# QuadPowerDistro_v0.net
KiCad netlist of a schematic drawn in EAGLE
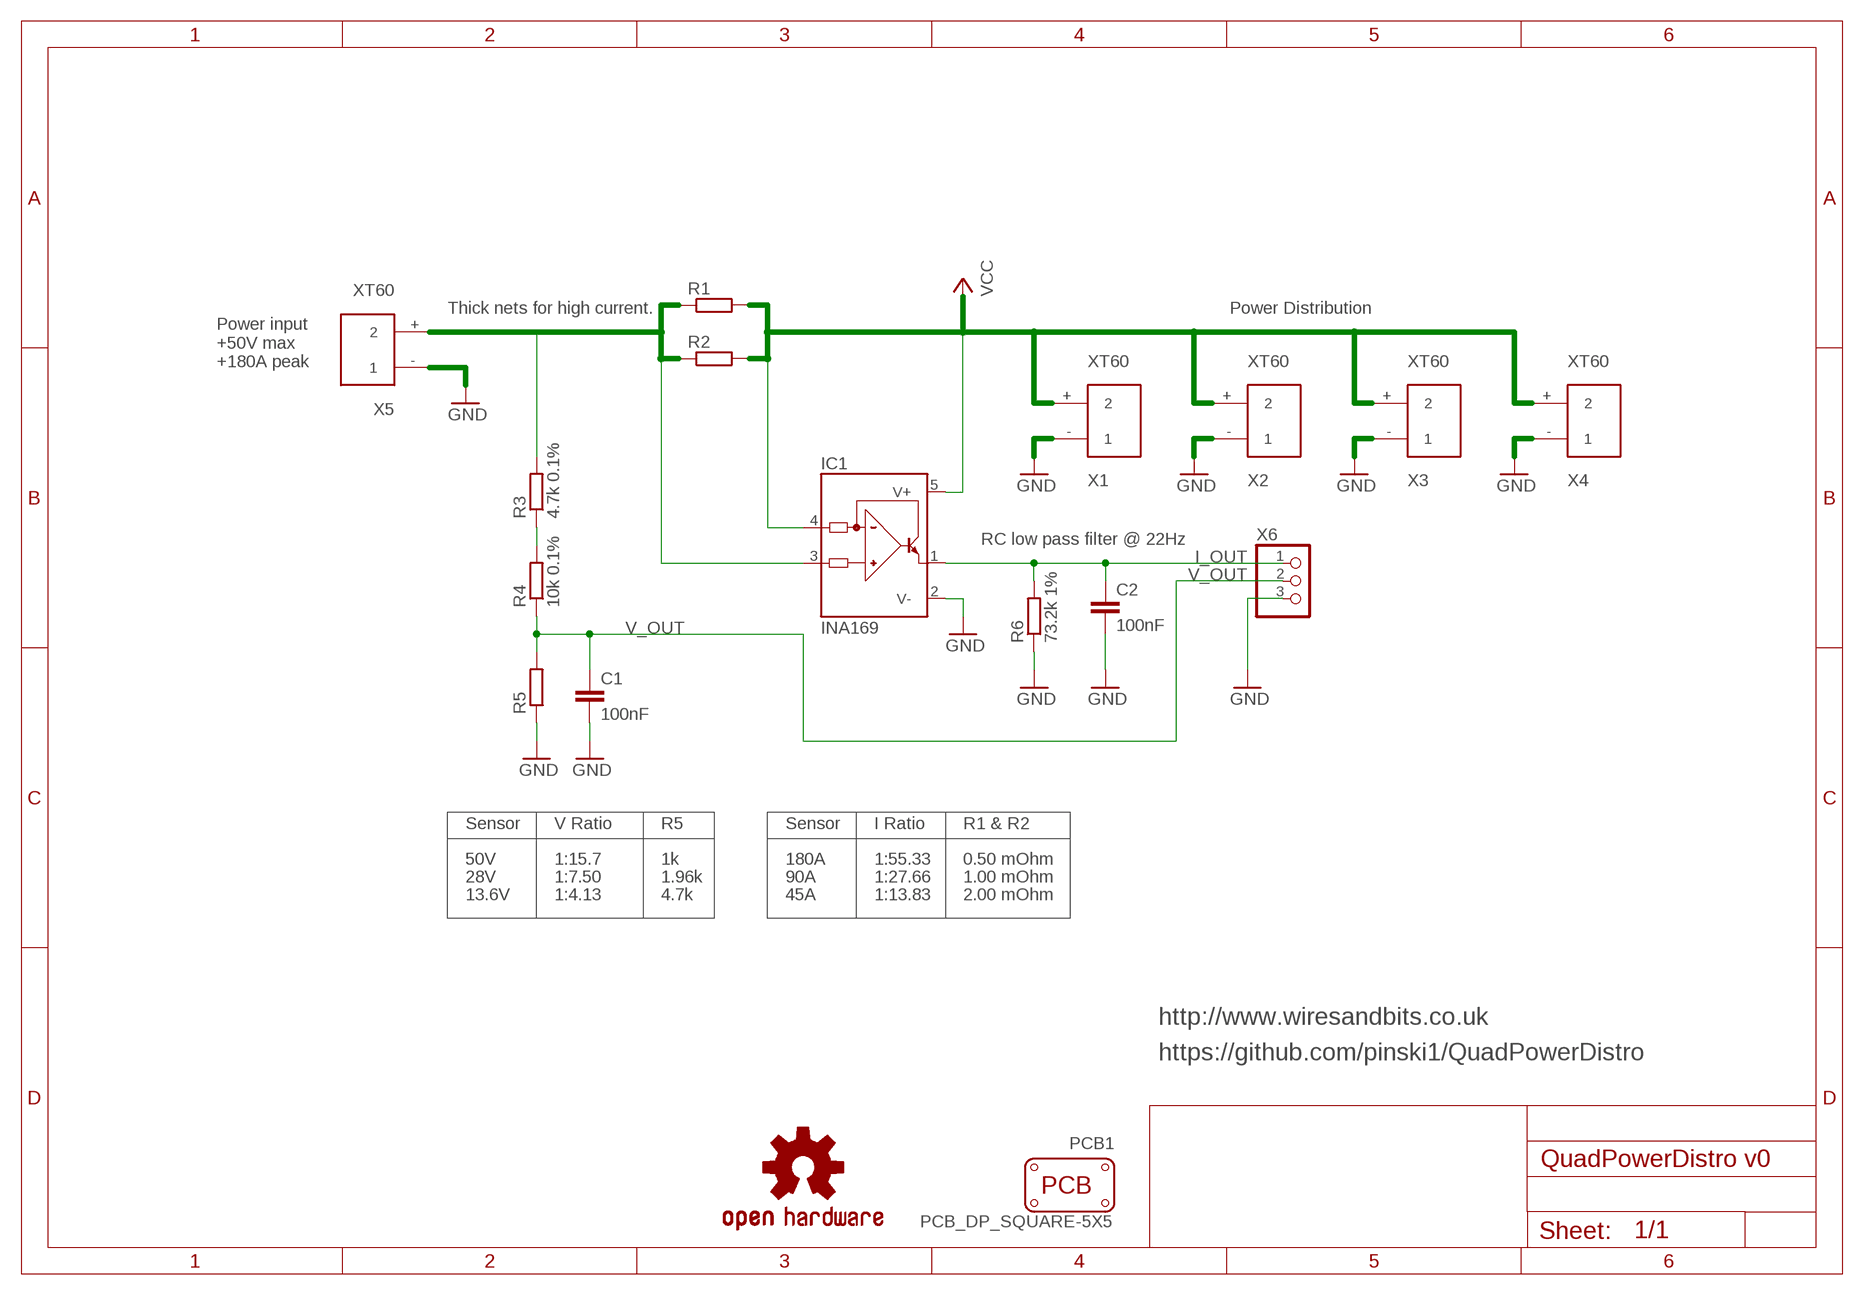
[diagram p0: schematic, sheet 1]

(export (version "E")
  (design (tool "Eeschema 10.0.6"))
  (components
    (comp (ref "C1")
      (value "100nF")
      (footprint "eagle-import:C0805")
      (fields (field (name "MF") "AVX") (field (name "MPN") "02016D104KAT2A"))
      (libsource (lib "eagle-import") (part "C-EUC0805"))
    )
    (comp (ref "C2")
      (value "100nF")
      (footprint "eagle-import:C0805")
      (fields (field (name "MF") "AVX") (field (name "MPN") "02016D104KAT2A"))
      (libsource (lib "eagle-import") (part "C-EUC0805"))
    )
    (comp (ref "IC1")
      (value "INA169")
      (footprint "eagle-import:SOT23-5")
      (fields (field (name "MF") "TEXAS INSTRUMENTS") (field (name "MPN") "INA169NA/250G4"))
      (libsource (lib "eagle-import") (part "INA168"))
    )
    (comp (ref "LOGO1")
      (value "OSHW-LOGOL")
      (footprint "eagle-import:OSHW-LOGO-L")
      (libsource (lib "eagle-import") (part "OSHW-LOGOL"))
    )
    (comp (ref "PCB1")
      (value "PCB_DP_SQUARE-5X5")
      (footprint "eagle-import:DP5050_V1")
      (libsource (lib "eagle-import") (part "PCB_DP_SQUARE-5X5"))
    )
    (comp (ref "R1")
      (value "R-EU_R2512")
      (footprint "eagle-import:R2512")
      (libsource (lib "eagle-import") (part "R-EU_R2512"))
    )
    (comp (ref "R2")
      (value "R-EU_R2512")
      (footprint "eagle-import:R2512")
      (libsource (lib "eagle-import") (part "R-EU_R2512"))
    )
    (comp (ref "R3")
      (value "4.7k 0.1%")
      (footprint "eagle-import:R0805")
      (fields (field (name "MF") "SUSUMU") (field (name "MPN") "RR1220P-472-B-T5"))
      (libsource (lib "eagle-import") (part "R-EU_R0805"))
    )
    (comp (ref "R4")
      (value "10k 0.1%")
      (footprint "eagle-import:R0805")
      (fields (field (name "MF") "SUSUMU") (field (name "MPN") "RR1220P-103-B-T5"))
      (libsource (lib "eagle-import") (part "R-EU_R0805"))
    )
    (comp (ref "R5")
      (value "R-EU_R0805")
      (footprint "eagle-import:R0805")
      (libsource (lib "eagle-import") (part "R-EU_R0805"))
    )
    (comp (ref "R6")
      (value "73.2k 1%")
      (footprint "eagle-import:R0805")
      (libsource (lib "eagle-import") (part "R-EU_R0805"))
    )
    (comp (ref "X1")
      (value "XT60")
      (footprint "eagle-import:XT60")
      (libsource (lib "eagle-import") (part "XT60"))
    )
    (comp (ref "X2")
      (value "XT60")
      (footprint "eagle-import:XT60")
      (libsource (lib "eagle-import") (part "XT60"))
    )
    (comp (ref "X3")
      (value "XT60")
      (footprint "eagle-import:XT60")
      (libsource (lib "eagle-import") (part "XT60"))
    )
    (comp (ref "X4")
      (value "XT60")
      (footprint "eagle-import:XT60")
      (libsource (lib "eagle-import") (part "XT60"))
    )
    (comp (ref "X5")
      (value "XT60")
      (footprint "eagle-import:XT60")
      (libsource (lib "eagle-import") (part "XT60"))
    )
    (comp (ref "X6")
      (value "PINHD-1X3")
      (footprint "eagle-import:1X03")
      (libsource (lib "eagle-import") (part "PINHD-1X3"))
    )
  )
  (nets
    (net (code "1") (name "/I_OUT") (class "Default")
      (node (ref "C2") (pin "1") (pinfunction "1_1") (pintype "passive"))
      (node (ref "IC1") (pin "1") (pinfunction "OUT_1") (pintype "output"))
      (node (ref "R6") (pin "2") (pinfunction "2_2") (pintype "passive"))
      (node (ref "X6") (pin "1") (pinfunction "1_1") (pintype "passive"))
    )
    (net (code "2") (name "/V_OUT") (class "Default")
      (node (ref "C1") (pin "1") (pinfunction "1_1") (pintype "passive"))
      (node (ref "R4") (pin "1") (pinfunction "1_1") (pintype "passive"))
      (node (ref "R5") (pin "2") (pinfunction "2_2") (pintype "passive"))
      (node (ref "X6") (pin "2") (pinfunction "2_2") (pintype "passive"))
    )
    (net (code "3") (name "GND") (class "Default")
      (node (ref "C1") (pin "2") (pinfunction "2_2") (pintype "passive"))
      (node (ref "C2") (pin "2") (pinfunction "2_2") (pintype "passive"))
      (node (ref "IC1") (pin "2") (pinfunction "V-_2") (pintype "power_in"))
      (node (ref "R5") (pin "1") (pinfunction "1_1") (pintype "passive"))
      (node (ref "R6") (pin "1") (pinfunction "1_1") (pintype "passive"))
      (node (ref "X1") (pin "-") (pinfunction "1_-") (pintype "bidirectional"))
      (node (ref "X2") (pin "-") (pinfunction "1_-") (pintype "bidirectional"))
      (node (ref "X3") (pin "-") (pinfunction "1_-") (pintype "bidirectional"))
      (node (ref "X4") (pin "-") (pinfunction "1_-") (pintype "bidirectional"))
      (node (ref "X5") (pin "-") (pinfunction "1_-") (pintype "bidirectional"))
      (node (ref "X6") (pin "3") (pinfunction "3_3") (pintype "passive"))
    )
    (net (code "4") (name "Net-(IC1-IN+)") (class "Default")
      (node (ref "IC1") (pin "3") (pinfunction "IN+_3") (pintype "input"))
      (node (ref "R1") (pin "1") (pinfunction "1_1") (pintype "passive"))
      (node (ref "R2") (pin "1") (pinfunction "1_1") (pintype "passive"))
      (node (ref "R3") (pin "2") (pinfunction "2_2") (pintype "passive"))
      (node (ref "X5") (pin "+") (pinfunction "2_+") (pintype "bidirectional"))
    )
    (net (code "5") (name "Net-(R3-Pad1)") (class "Default")
      (node (ref "R3") (pin "1") (pinfunction "1_1") (pintype "passive"))
      (node (ref "R4") (pin "2") (pinfunction "2_2") (pintype "passive"))
    )
    (net (code "6") (name "VCC") (class "Default")
      (node (ref "IC1") (pin "4") (pinfunction "IN-_4") (pintype "input"))
      (node (ref "IC1") (pin "5") (pinfunction "V+_5") (pintype "power_in"))
      (node (ref "R1") (pin "2") (pinfunction "2_2") (pintype "passive"))
      (node (ref "R2") (pin "2") (pinfunction "2_2") (pintype "passive"))
      (node (ref "X1") (pin "+") (pinfunction "2_+") (pintype "bidirectional"))
      (node (ref "X2") (pin "+") (pinfunction "2_+") (pintype "bidirectional"))
      (node (ref "X3") (pin "+") (pinfunction "2_+") (pintype "bidirectional"))
      (node (ref "X4") (pin "+") (pinfunction "2_+") (pintype "bidirectional"))
    )
  )
)
